# Sheet1.net
KiCad netlist of a schematic drawn in Altium Designer
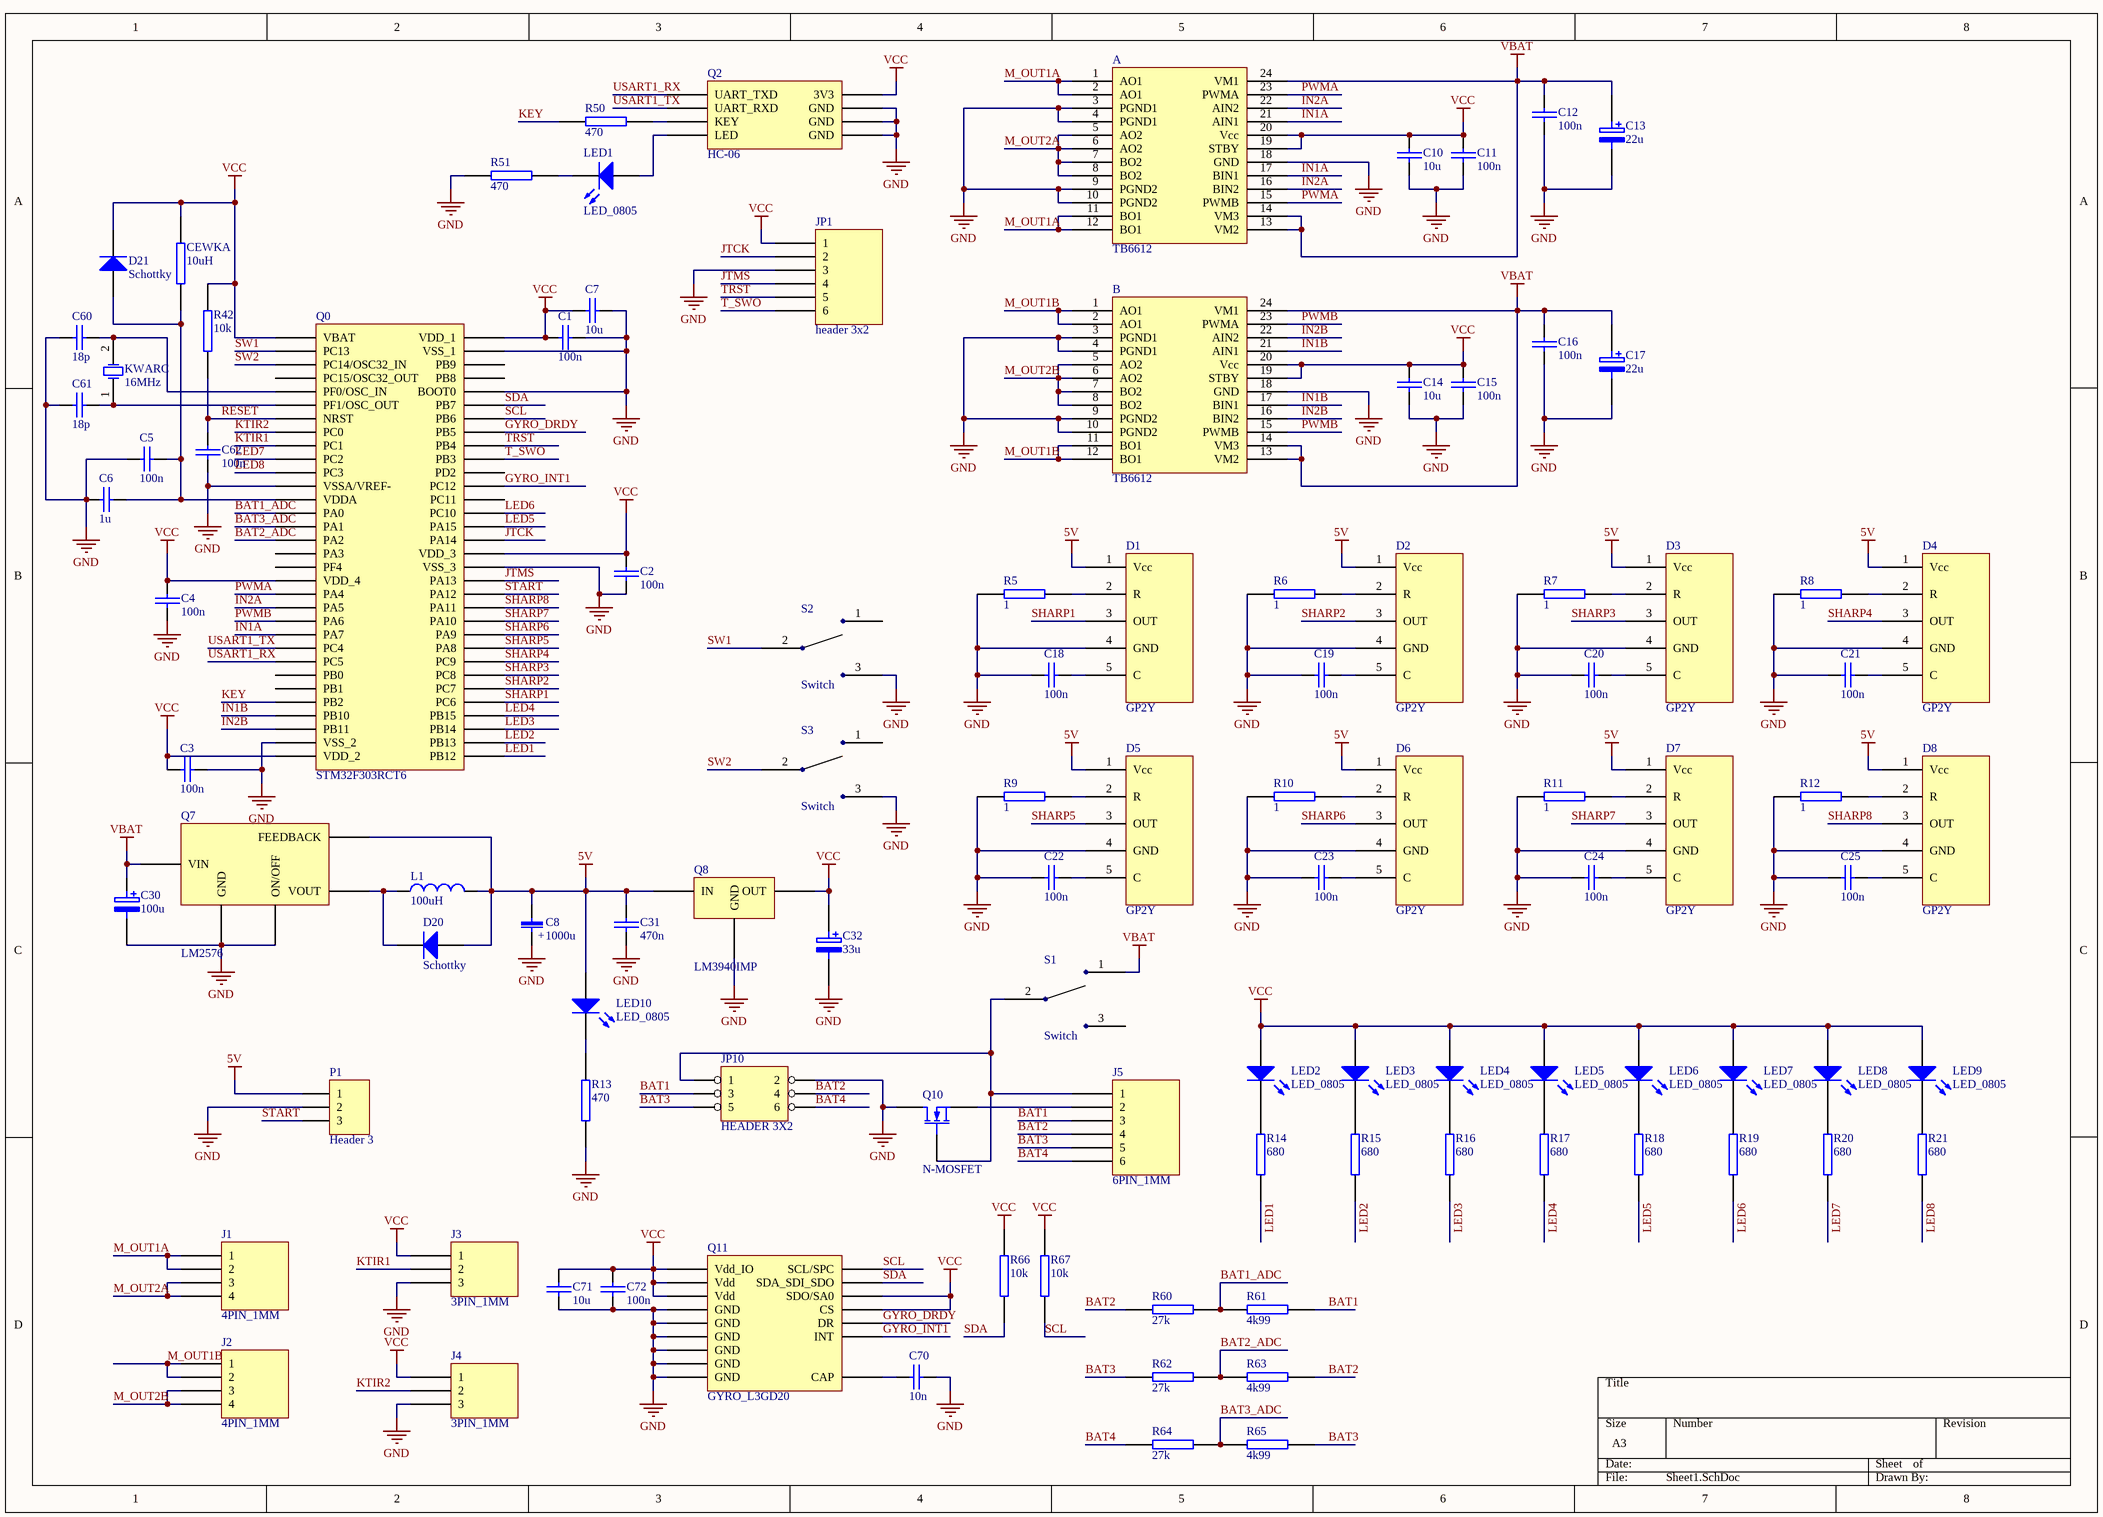
[diagram p0: Sheet1.SchDoc]

(export (version "E")
  (design (tool "Eeschema 10.0.6"))
  (components
    (comp (ref "A")
      (value "TB6612")
      (footprint "SSOP24")
      (libsource (lib "Integrated_Library1") (part "TB6612"))
    )
    (comp (ref "B")
      (value "TB6612")
      (footprint "SSOP24")
      (libsource (lib "Integrated_Library1") (part "TB6612"))
    )
    (comp (ref "C1")
      (value "100n")
      (footprint "0805 CAP")
      (description "Capacitor")
      (libsource (lib "Integrated_Library1") (part "CAP"))
    )
    (comp (ref "C2")
      (value "100n")
      (footprint "0805 CAP")
      (description "Capacitor")
      (libsource (lib "Integrated_Library1") (part "CAP"))
    )
    (comp (ref "C3")
      (value "100n")
      (footprint "0805 CAP")
      (description "Capacitor")
      (libsource (lib "Integrated_Library1") (part "CAP"))
    )
    (comp (ref "C4")
      (value "100n")
      (footprint "0805 CAP")
      (description "Capacitor")
      (libsource (lib "Integrated_Library1") (part "CAP"))
    )
    (comp (ref "C5")
      (value "100n")
      (footprint "0805 CAP")
      (description "Capacitor")
      (libsource (lib "Integrated_Library1") (part "CAP"))
    )
    (comp (ref "C6")
      (value "1u")
      (footprint "0805 CAP")
      (description "Capacitor")
      (libsource (lib "Integrated_Library1") (part "CAP"))
    )
    (comp (ref "C7")
      (value "10u")
      (footprint "0805 CAP")
      (description "Capacitor")
      (libsource (lib "Integrated_Library1") (part "CAP"))
    )
    (comp (ref "C8")
      (value "1000u")
      (footprint "F720J108MMC")
      (description "F720J108MMC")
      (libsource (lib "F720J108MMC") (part "1000u"))
    )
    (comp (ref "C10")
      (value "10u")
      (footprint "0805 CAP")
      (description "Capacitor")
      (libsource (lib "Integrated_Library1") (part "CAP"))
    )
    (comp (ref "C11")
      (value "100n")
      (footprint "0805 CAP")
      (description "Capacitor")
      (libsource (lib "Integrated_Library1") (part "CAP"))
    )
    (comp (ref "C12")
      (value "100n")
      (footprint "0805 CAP")
      (description "Capacitor")
      (libsource (lib "Integrated_Library1") (part "CAP"))
    )
    (comp (ref "C13") (value "22u") (footprint "TANTAL_A") (libsource (lib "Integrated_Library1") (part "E")))
    (comp (ref "C14")
      (value "10u")
      (footprint "0805 CAP")
      (description "Capacitor")
      (libsource (lib "Integrated_Library1") (part "CAP"))
    )
    (comp (ref "C15")
      (value "100n")
      (footprint "0805 CAP")
      (description "Capacitor")
      (libsource (lib "Integrated_Library1") (part "CAP"))
    )
    (comp (ref "C16")
      (value "100n")
      (footprint "0805 CAP")
      (description "Capacitor")
      (libsource (lib "Integrated_Library1") (part "CAP"))
    )
    (comp (ref "C17") (value "22u") (footprint "TANTAL_A") (libsource (lib "Integrated_Library1") (part "E")))
    (comp (ref "C18")
      (value "100n")
      (footprint "0805 CAP")
      (description "Capacitor")
      (libsource (lib "Integrated_Library1") (part "CAP"))
    )
    (comp (ref "C19")
      (value "100n")
      (footprint "0805 CAP")
      (description "Capacitor")
      (libsource (lib "Integrated_Library1") (part "CAP"))
    )
    (comp (ref "C20")
      (value "100n")
      (footprint "0805 CAP")
      (description "Capacitor")
      (libsource (lib "Integrated_Library1") (part "CAP"))
    )
    (comp (ref "C21")
      (value "100n")
      (footprint "0805 CAP")
      (description "Capacitor")
      (libsource (lib "Integrated_Library1") (part "CAP"))
    )
    (comp (ref "C22")
      (value "100n")
      (footprint "0805 CAP")
      (description "Capacitor")
      (libsource (lib "Integrated_Library1") (part "CAP"))
    )
    (comp (ref "C23")
      (value "100n")
      (footprint "0805 CAP")
      (description "Capacitor")
      (libsource (lib "Integrated_Library1") (part "CAP"))
    )
    (comp (ref "C24")
      (value "100n")
      (footprint "0805 CAP")
      (description "Capacitor")
      (libsource (lib "Integrated_Library1") (part "CAP"))
    )
    (comp (ref "C25")
      (value "100n")
      (footprint "0805 CAP")
      (description "Capacitor")
      (libsource (lib "Integrated_Library1") (part "CAP"))
    )
    (comp (ref "C30")
      (value "100u")
      (footprint "TANTAL_C")
      (description "Electrolytic Capacitor")
      (libsource (lib "Integrated_Library1") (part "ELECTRO2"))
    )
    (comp (ref "C31")
      (value "470n")
      (footprint "0805 CAP")
      (description "Capacitor")
      (libsource (lib "Integrated_Library1") (part "CAP"))
    )
    (comp (ref "C32")
      (value "33u")
      (footprint "TANTAL_C")
      (description "Electrolytic Capacitor")
      (libsource (lib "Integrated_Library1") (part "ELECTRO2"))
    )
    (comp (ref "C60")
      (value "18p")
      (footprint "0805 CAP")
      (description "Capacitor")
      (libsource (lib "Integrated_Library1") (part "CAP"))
    )
    (comp (ref "C61")
      (value "18p")
      (footprint "0805 CAP")
      (description "Capacitor")
      (libsource (lib "Integrated_Library1") (part "CAP"))
    )
    (comp (ref "C62")
      (value "100n")
      (footprint "0805 CAP")
      (description "Capacitor")
      (libsource (lib "Integrated_Library1") (part "CAP"))
    )
    (comp (ref "C70")
      (value "10n")
      (footprint "0805")
      (description "Capacitor")
      (libsource (lib "Integrated_Library1") (part "CAP"))
    )
    (comp (ref "C71")
      (value "10u")
      (footprint "0805")
      (description "Capacitor")
      (libsource (lib "Integrated_Library1") (part "CAP"))
    )
    (comp (ref "C72")
      (value "100n")
      (footprint "0805")
      (description "Capacitor")
      (libsource (lib "Integrated_Library1") (part "CAP"))
    )
    (comp (ref "CEWKA") (value "10uH") (footprint "0805") (libsource (lib "Integrated_Library1") (part "R")))
    (comp (ref "D1")
      (value "GP2Y")
      (footprint "gp2y smd")
      (libsource (lib "Integrated_Library1") (part "GP2Y"))
    )
    (comp (ref "D2")
      (value "GP2Y")
      (footprint "gp2y smd")
      (libsource (lib "Integrated_Library1") (part "GP2Y"))
    )
    (comp (ref "D3")
      (value "GP2Y")
      (footprint "gp2y smd")
      (libsource (lib "Integrated_Library1") (part "GP2Y"))
    )
    (comp (ref "D4")
      (value "GP2Y")
      (footprint "gp2y smd")
      (libsource (lib "Integrated_Library1") (part "GP2Y"))
    )
    (comp (ref "D5")
      (value "GP2Y")
      (footprint "gp2y smd")
      (libsource (lib "Integrated_Library1") (part "GP2Y"))
    )
    (comp (ref "D6")
      (value "GP2Y")
      (footprint "gp2y smd")
      (libsource (lib "Integrated_Library1") (part "GP2Y"))
    )
    (comp (ref "D7")
      (value "GP2Y")
      (footprint "gp2y smd")
      (libsource (lib "Integrated_Library1") (part "GP2Y"))
    )
    (comp (ref "D8")
      (value "GP2Y")
      (footprint "gp2y smd")
      (libsource (lib "Integrated_Library1") (part "GP2Y"))
    )
    (comp (ref "D20") (value "Schottky") (footprint "SMB") (libsource (lib "juziuLibrary") (part "Schottky")))
    (comp (ref "D21") (value "Schottky") (footprint "SMB") (libsource (lib "juziuLibrary") (part "Schottky")))
    (comp (ref "J1")
      (value "4PIN_1MM")
      (footprint "CON_1mm_4pin")
      (libsource (lib "juziuLibrary") (part "CON_1MM_4PIN"))
    )
    (comp (ref "J2")
      (value "4PIN_1MM")
      (footprint "CON_1mm_4pin")
      (libsource (lib "juziuLibrary") (part "CON_1MM_4PIN"))
    )
    (comp (ref "J3")
      (value "3PIN_1MM")
      (footprint "CON_1MM_3PIN")
      (libsource (lib "juziuLibrary") (part "CON_1MM_3PIN"))
    )
    (comp (ref "J4")
      (value "3PIN_1MM")
      (footprint "CON_1MM_3PIN")
      (libsource (lib "juziuLibrary") (part "CON_1MM_3PIN"))
    )
    (comp (ref "J5")
      (value "6PIN_1MM")
      (footprint "6pin")
      (libsource (lib "juziuLibrary") (part "CON_1MM_6PIN"))
    )
    (comp (ref "JP1")
      (value "header 3x2")
      (footprint "MM3X2 SMD")
      (libsource (lib "juziuLibrary") (part "CON_1MM_6PIN"))
    )
    (comp (ref "JP10")
      (value "HEADER 3X2")
      (footprint "MM3X2 SMD")
      (libsource (lib "Integrated_Library1") (part "HEADER 3X2"))
    )
    (comp (ref "KWARC")
      (value "16MHz")
      (footprint "KWARC_16M")
      (description "Crystal Oscillator")
      (fields (field (name "PUBLISHER") "Altium Limited"))
      (libsource (lib "juziuLibrary") (part "XTAL"))
    )
    (comp (ref "L1") (value "100uH") (footprint "CEWKA") (libsource (lib "juziuLibrary") (part "CEWKA")))
    (comp (ref "LED1")
      (value "LED_0805")
      (footprint "0805")
      (libsource (lib "juziuLibrary") (part "LED_0805"))
    )
    (comp (ref "LED2")
      (value "LED_0805")
      (footprint "0805")
      (libsource (lib "juziuLibrary") (part "LED_0805"))
    )
    (comp (ref "LED3")
      (value "LED_0805")
      (footprint "0805")
      (libsource (lib "juziuLibrary") (part "LED_0805"))
    )
    (comp (ref "LED4")
      (value "LED_0805")
      (footprint "0805")
      (libsource (lib "juziuLibrary") (part "LED_0805"))
    )
    (comp (ref "LED5")
      (value "LED_0805")
      (footprint "0805")
      (libsource (lib "juziuLibrary") (part "LED_0805"))
    )
    (comp (ref "LED6")
      (value "LED_0805")
      (footprint "0805")
      (libsource (lib "juziuLibrary") (part "LED_0805"))
    )
    (comp (ref "LED7")
      (value "LED_0805")
      (footprint "0805")
      (libsource (lib "juziuLibrary") (part "LED_0805"))
    )
    (comp (ref "LED8")
      (value "LED_0805")
      (footprint "0805")
      (libsource (lib "juziuLibrary") (part "LED_0805"))
    )
    (comp (ref "LED9")
      (value "LED_0805")
      (footprint "0805")
      (libsource (lib "juziuLibrary") (part "LED_0805"))
    )
    (comp (ref "LED10")
      (value "LED_0805")
      (footprint "0805")
      (libsource (lib "juziuLibrary") (part "LED_0805"))
    )
    (comp (ref "P1")
      (value "Header 3")
      (footprint "HDR1X3")
      (description "Header, 3-Pin")
      (fields (field (name "PUBLISHER") "Altium Limited"))
      (libsource (lib "Miscellaneous Connectors") (part "Header 3"))
    )
    (comp (ref "Q0")
      (value "STM32F303RCT6")
      (footprint "STM32F303RCT6")
      (libsource (lib "STM32F303TRCT6") (part "STM32F303RCT6"))
    )
    (comp (ref "Q2")
      (value "HC-06")
      (footprint "PCBComponent_1")
      (description "Bluetooth")
      (libsource (lib "juziuLibrary") (part "Component_1"))
    )
    (comp (ref "Q7") (value "LM2576") (footprint "LM2576") (libsource (lib "juziuLibrary") (part "LM2576")))
    (comp (ref "Q8")
      (value "LM3940IMP")
      (footprint "LM3940IMP")
      (libsource (lib "juziuLibrary") (part "LM3940IMP"))
    )
    (comp (ref "Q10")
      (value "N-MOSFET")
      (footprint "DPAK")
      (libsource (lib "juziuLibrary") (part "n-mosfet"))
    )
    (comp (ref "Q11")
      (value "GYRO_L3GD20")
      (footprint "GYRO_L3GD20")
      (libsource (lib "juziuLibrary") (part "GYRO_L3GD20"))
    )
    (comp (ref "R5") (value "1") (footprint "0805 RES") (libsource (lib "Integrated_Library1") (part "R")))
    (comp (ref "R6") (value "1") (footprint "0805 RES") (libsource (lib "Integrated_Library1") (part "R")))
    (comp (ref "R7") (value "1") (footprint "0805 RES") (libsource (lib "Integrated_Library1") (part "R")))
    (comp (ref "R8") (value "1") (footprint "0805 RES") (libsource (lib "Integrated_Library1") (part "R")))
    (comp (ref "R9") (value "1") (footprint "0805 RES") (libsource (lib "Integrated_Library1") (part "R")))
    (comp (ref "R10") (value "1") (footprint "0805 RES") (libsource (lib "Integrated_Library1") (part "R")))
    (comp (ref "R11") (value "1") (footprint "0805 RES") (libsource (lib "Integrated_Library1") (part "R")))
    (comp (ref "R12") (value "1") (footprint "0805 RES") (libsource (lib "Integrated_Library1") (part "R")))
    (comp (ref "R13") (value "470") (footprint "0805 RES") (libsource (lib "Integrated_Library1") (part "R")))
    (comp (ref "R14") (value "680") (footprint "0805 RES") (libsource (lib "Integrated_Library1") (part "R")))
    (comp (ref "R15") (value "680") (footprint "0805 RES") (libsource (lib "Integrated_Library1") (part "R")))
    (comp (ref "R16") (value "680") (footprint "0805 RES") (libsource (lib "Integrated_Library1") (part "R")))
    (comp (ref "R17") (value "680") (footprint "0805 RES") (libsource (lib "Integrated_Library1") (part "R")))
    (comp (ref "R18") (value "680") (footprint "0805 RES") (libsource (lib "Integrated_Library1") (part "R")))
    (comp (ref "R19") (value "680") (footprint "0805 RES") (libsource (lib "Integrated_Library1") (part "R")))
    (comp (ref "R20") (value "680") (footprint "0805 RES") (libsource (lib "Integrated_Library1") (part "R")))
    (comp (ref "R21") (value "680") (footprint "0805 RES") (libsource (lib "Integrated_Library1") (part "R")))
    (comp (ref "R42") (value "10k") (footprint "0805") (libsource (lib "Integrated_Library1") (part "R")))
    (comp (ref "R50") (value "470") (footprint "0805 RES") (libsource (lib "Integrated_Library1") (part "R")))
    (comp (ref "R51") (value "470") (footprint "0805 RES") (libsource (lib "Integrated_Library1") (part "R")))
    (comp (ref "R60") (value "27k") (footprint "0805") (libsource (lib "Integrated_Library1") (part "R")))
    (comp (ref "R61") (value "4k99") (footprint "0805") (libsource (lib "Integrated_Library1") (part "R")))
    (comp (ref "R62") (value "27k") (footprint "0805") (libsource (lib "Integrated_Library1") (part "R")))
    (comp (ref "R63") (value "4k99") (footprint "0805") (libsource (lib "Integrated_Library1") (part "R")))
    (comp (ref "R64") (value "27k") (footprint "0805") (libsource (lib "Integrated_Library1") (part "R")))
    (comp (ref "R65") (value "4k99") (footprint "0805") (libsource (lib "Integrated_Library1") (part "R")))
    (comp (ref "R66") (value "10k") (footprint "0805") (libsource (lib "Integrated_Library1") (part "R")))
    (comp (ref "R67") (value "10k") (footprint "0805") (libsource (lib "Integrated_Library1") (part "R")))
    (comp (ref "S1") (value "Switch") (footprint "Switch") (libsource (lib "juziuLibrary") (part "Switch")))
    (comp (ref "S2") (value "Switch") (footprint "Switch") (libsource (lib "juziuLibrary") (part "Switch")))
    (comp (ref "S3") (value "Switch") (footprint "Switch") (libsource (lib "juziuLibrary") (part "Switch")))
  )
  (nets
    (net (code "1") (name "/BAT1") (class "Default")
      (node (ref "J5") (pin "3") (pinfunction "3_3") (pintype "passive"))
      (node (ref "JP10") (pin "3") (pinfunction "3_3") (pintype "passive"))
      (node (ref "R61") (pin "1") (pinfunction "1_1") (pintype "passive"))
    )
    (net (code "2") (name "/BAT1_ADC") (class "Default")
      (node (ref "Q0") (pin "14") (pinfunction "PA0_14") (pintype "passive"))
      (node (ref "R60") (pin "1") (pinfunction "1_1") (pintype "passive"))
      (node (ref "R61") (pin "2") (pinfunction "2_2") (pintype "passive"))
    )
    (net (code "3") (name "/BAT2") (class "Default")
      (node (ref "J5") (pin "4") (pinfunction "4_4") (pintype "passive"))
      (node (ref "JP10") (pin "4") (pinfunction "4_4") (pintype "passive"))
      (node (ref "R60") (pin "2") (pinfunction "2_2") (pintype "passive"))
      (node (ref "R63") (pin "1") (pinfunction "1_1") (pintype "passive"))
    )
    (net (code "4") (name "/BAT2_ADC") (class "Default")
      (node (ref "Q0") (pin "16") (pinfunction "PA2_16") (pintype "passive"))
      (node (ref "R62") (pin "1") (pinfunction "1_1") (pintype "passive"))
      (node (ref "R63") (pin "2") (pinfunction "2_2") (pintype "passive"))
    )
    (net (code "5") (name "/BAT3") (class "Default")
      (node (ref "J5") (pin "5") (pinfunction "5_5") (pintype "passive"))
      (node (ref "JP10") (pin "5") (pinfunction "5_5") (pintype "passive"))
      (node (ref "R62") (pin "2") (pinfunction "2_2") (pintype "passive"))
      (node (ref "R65") (pin "1") (pinfunction "1_1") (pintype "passive"))
    )
    (net (code "6") (name "/BAT3_ADC") (class "Default")
      (node (ref "Q0") (pin "15") (pinfunction "PA1_15") (pintype "passive"))
      (node (ref "R64") (pin "1") (pinfunction "1_1") (pintype "passive"))
      (node (ref "R65") (pin "2") (pinfunction "2_2") (pintype "passive"))
    )
    (net (code "7") (name "/BAT4") (class "Default")
      (node (ref "J5") (pin "6") (pinfunction "6_6") (pintype "passive"))
      (node (ref "JP10") (pin "6") (pinfunction "6_6") (pintype "passive"))
      (node (ref "R64") (pin "2") (pinfunction "2_2") (pintype "passive"))
    )
    (net (code "8") (name "/GYRO_DRDY") (class "Default")
      (node (ref "Q0") (pin "57") (pinfunction "PB5_57") (pintype "passive"))
      (node (ref "Q11") (pin "6") (pinfunction "DR_6") (pintype "passive"))
    )
    (net (code "9") (name "/GYRO_INT1") (class "Default")
      (node (ref "Q0") (pin "53") (pinfunction "PC12_53") (pintype "passive"))
      (node (ref "Q11") (pin "7") (pinfunction "INT_7") (pintype "passive"))
    )
    (net (code "10") (name "/IN1A") (class "Default")
      (node (ref "A") (pin "17") (pinfunction "BIN1_17") (pintype "passive"))
      (node (ref "A") (pin "21") (pinfunction "AIN1_21") (pintype "passive"))
      (node (ref "Q0") (pin "23") (pinfunction "PA7_23") (pintype "passive"))
    )
    (net (code "11") (name "/IN1B") (class "Default")
      (node (ref "B") (pin "17") (pinfunction "BIN1_17") (pintype "passive"))
      (node (ref "B") (pin "21") (pinfunction "AIN1_21") (pintype "passive"))
      (node (ref "Q0") (pin "29") (pinfunction "PB10_29") (pintype "passive"))
    )
    (net (code "12") (name "/IN2A") (class "Default")
      (node (ref "A") (pin "16") (pinfunction "BIN2_16") (pintype "passive"))
      (node (ref "A") (pin "22") (pinfunction "AIN2_22") (pintype "passive"))
      (node (ref "Q0") (pin "21") (pinfunction "PA5_21") (pintype "passive"))
    )
    (net (code "13") (name "/IN2B") (class "Default")
      (node (ref "B") (pin "16") (pinfunction "BIN2_16") (pintype "passive"))
      (node (ref "B") (pin "22") (pinfunction "AIN2_22") (pintype "passive"))
      (node (ref "Q0") (pin "30") (pinfunction "PB11_30") (pintype "passive"))
    )
    (net (code "14") (name "/JTCK") (class "Default")
      (node (ref "JP1") (pin "2") (pinfunction "2_2") (pintype "passive"))
      (node (ref "Q0") (pin "49") (pinfunction "PA14_49") (pintype "passive"))
    )
    (net (code "15") (name "/JTMS") (class "Default")
      (node (ref "JP1") (pin "4") (pinfunction "4_4") (pintype "passive"))
      (node (ref "Q0") (pin "46") (pinfunction "PA13_46") (pintype "passive"))
    )
    (net (code "16") (name "/KEY") (class "Default")
      (node (ref "Q0") (pin "28") (pinfunction "PB2_28") (pintype "passive"))
      (node (ref "R50") (pin "1") (pinfunction "1_1") (pintype "passive"))
    )
    (net (code "17") (name "/KTIR1") (class "Default")
      (node (ref "J3") (pin "2") (pinfunction "2_2") (pintype "passive"))
      (node (ref "Q0") (pin "9") (pinfunction "PC1_9") (pintype "passive"))
    )
    (net (code "18") (name "/KTIR2") (class "Default")
      (node (ref "J4") (pin "2") (pinfunction "2_2") (pintype "passive"))
      (node (ref "Q0") (pin "8") (pinfunction "PC0_8") (pintype "passive"))
    )
    (net (code "19") (name "/LED1") (class "Default")
      (node (ref "Q0") (pin "33") (pinfunction "PB12_33") (pintype "passive"))
      (node (ref "R14") (pin "1") (pinfunction "1_1") (pintype "passive"))
    )
    (net (code "20") (name "/LED2") (class "Default")
      (node (ref "Q0") (pin "34") (pinfunction "PB13_34") (pintype "passive"))
      (node (ref "R15") (pin "1") (pinfunction "1_1") (pintype "passive"))
    )
    (net (code "21") (name "/LED3") (class "Default")
      (node (ref "Q0") (pin "35") (pinfunction "PB14_35") (pintype "passive"))
      (node (ref "R16") (pin "1") (pinfunction "1_1") (pintype "passive"))
    )
    (net (code "22") (name "/LED4") (class "Default")
      (node (ref "Q0") (pin "36") (pinfunction "PB15_36") (pintype "passive"))
      (node (ref "R17") (pin "1") (pinfunction "1_1") (pintype "passive"))
    )
    (net (code "23") (name "/LED5") (class "Default")
      (node (ref "Q0") (pin "50") (pinfunction "PA15_50") (pintype "passive"))
      (node (ref "R18") (pin "1") (pinfunction "1_1") (pintype "passive"))
    )
    (net (code "24") (name "/LED6") (class "Default")
      (node (ref "Q0") (pin "51") (pinfunction "PC10_51") (pintype "passive"))
      (node (ref "R19") (pin "1") (pinfunction "1_1") (pintype "passive"))
    )
    (net (code "25") (name "/LED7") (class "Default")
      (node (ref "Q0") (pin "10") (pinfunction "PC2_10") (pintype "passive"))
      (node (ref "R20") (pin "1") (pinfunction "1_1") (pintype "passive"))
    )
    (net (code "26") (name "/LED8") (class "Default")
      (node (ref "Q0") (pin "11") (pinfunction "PC3_11") (pintype "passive"))
      (node (ref "R21") (pin "1") (pinfunction "1_1") (pintype "passive"))
    )
    (net (code "27") (name "/M_OUT1A") (class "Default")
      (node (ref "A") (pin "1") (pinfunction "AO1_1") (pintype "passive"))
      (node (ref "A") (pin "11") (pinfunction "BO1_11") (pintype "passive"))
      (node (ref "A") (pin "12") (pinfunction "BO1_12") (pintype "passive"))
      (node (ref "A") (pin "2") (pinfunction "AO1_2") (pintype "passive"))
      (node (ref "J1") (pin "1") (pinfunction "1_1") (pintype "passive"))
      (node (ref "J1") (pin "2") (pinfunction "2_2") (pintype "passive"))
    )
    (net (code "28") (name "/M_OUT1B") (class "Default")
      (node (ref "B") (pin "1") (pinfunction "AO1_1") (pintype "passive"))
      (node (ref "B") (pin "11") (pinfunction "BO1_11") (pintype "passive"))
      (node (ref "B") (pin "12") (pinfunction "BO1_12") (pintype "passive"))
      (node (ref "B") (pin "2") (pinfunction "AO1_2") (pintype "passive"))
      (node (ref "J2") (pin "1") (pinfunction "1_1") (pintype "passive"))
      (node (ref "J2") (pin "2") (pinfunction "2_2") (pintype "passive"))
    )
    (net (code "29") (name "/M_OUT2A") (class "Default")
      (node (ref "A") (pin "5") (pinfunction "AO2_5") (pintype "passive"))
      (node (ref "A") (pin "6") (pinfunction "AO2_6") (pintype "passive"))
      (node (ref "A") (pin "7") (pinfunction "BO2_7") (pintype "passive"))
      (node (ref "A") (pin "8") (pinfunction "BO2_8") (pintype "passive"))
      (node (ref "J1") (pin "3") (pinfunction "3_3") (pintype "passive"))
      (node (ref "J1") (pin "4") (pinfunction "4_4") (pintype "passive"))
    )
    (net (code "30") (name "/M_OUT2B") (class "Default")
      (node (ref "B") (pin "5") (pinfunction "AO2_5") (pintype "passive"))
      (node (ref "B") (pin "6") (pinfunction "AO2_6") (pintype "passive"))
      (node (ref "B") (pin "7") (pinfunction "BO2_7") (pintype "passive"))
      (node (ref "B") (pin "8") (pinfunction "BO2_8") (pintype "passive"))
      (node (ref "J2") (pin "3") (pinfunction "3_3") (pintype "passive"))
      (node (ref "J2") (pin "4") (pinfunction "4_4") (pintype "passive"))
    )
    (net (code "31") (name "/PWMA") (class "Default")
      (node (ref "A") (pin "15") (pinfunction "PWMB_15") (pintype "passive"))
      (node (ref "A") (pin "23") (pinfunction "PWMA_23") (pintype "passive"))
      (node (ref "Q0") (pin "20") (pinfunction "PA4_20") (pintype "passive"))
    )
    (net (code "32") (name "/PWMB") (class "Default")
      (node (ref "B") (pin "15") (pinfunction "PWMB_15") (pintype "passive"))
      (node (ref "B") (pin "23") (pinfunction "PWMA_23") (pintype "passive"))
      (node (ref "Q0") (pin "22") (pinfunction "PA6_22") (pintype "passive"))
    )
    (net (code "33") (name "/RESET") (class "Default")
      (node (ref "C62") (pin "1") (pinfunction "1_1") (pintype "passive"))
      (node (ref "Q0") (pin "7") (pinfunction "NRST_7") (pintype "passive"))
      (node (ref "R42") (pin "1") (pinfunction "1_1") (pintype "passive"))
    )
    (net (code "34") (name "/SCL") (class "Default")
      (node (ref "Q0") (pin "58") (pinfunction "PB6_58") (pintype "passive"))
      (node (ref "Q11") (pin "2") (pinfunction "SCL/SPC_2") (pintype "passive"))
      (node (ref "R67") (pin "2") (pinfunction "2_2") (pintype "passive"))
    )
    (net (code "35") (name "/SDA") (class "Default")
      (node (ref "Q0") (pin "59") (pinfunction "PB7_59") (pintype "passive"))
      (node (ref "Q11") (pin "3") (pinfunction "SDA_SDI_SDO_3") (pintype "passive"))
      (node (ref "R66") (pin "2") (pinfunction "2_2") (pintype "passive"))
    )
    (net (code "36") (name "/SHARP1") (class "Default")
      (node (ref "D1") (pin "3") (pinfunction "OUT_3") (pintype "passive"))
      (node (ref "Q0") (pin "37") (pinfunction "PC6_37") (pintype "passive"))
    )
    (net (code "37") (name "/SHARP2") (class "Default")
      (node (ref "D2") (pin "3") (pinfunction "OUT_3") (pintype "passive"))
      (node (ref "Q0") (pin "38") (pinfunction "PC7_38") (pintype "passive"))
    )
    (net (code "38") (name "/SHARP3") (class "Default")
      (node (ref "D3") (pin "3") (pinfunction "OUT_3") (pintype "passive"))
      (node (ref "Q0") (pin "39") (pinfunction "PC8_39") (pintype "passive"))
    )
    (net (code "39") (name "/SHARP4") (class "Default")
      (node (ref "D4") (pin "3") (pinfunction "OUT_3") (pintype "passive"))
      (node (ref "Q0") (pin "40") (pinfunction "PC9_40") (pintype "passive"))
    )
    (net (code "40") (name "/SHARP5") (class "Default")
      (node (ref "D5") (pin "3") (pinfunction "OUT_3") (pintype "passive"))
      (node (ref "Q0") (pin "41") (pinfunction "PA8_41") (pintype "passive"))
    )
    (net (code "41") (name "/SHARP6") (class "Default")
      (node (ref "D6") (pin "3") (pinfunction "OUT_3") (pintype "passive"))
      (node (ref "Q0") (pin "42") (pinfunction "PA9_42") (pintype "passive"))
    )
    (net (code "42") (name "/SHARP7") (class "Default")
      (node (ref "D7") (pin "3") (pinfunction "OUT_3") (pintype "passive"))
      (node (ref "Q0") (pin "43") (pinfunction "PA10_43") (pintype "passive"))
    )
    (net (code "43") (name "/SHARP8") (class "Default")
      (node (ref "D8") (pin "3") (pinfunction "OUT_3") (pintype "passive"))
      (node (ref "Q0") (pin "44") (pinfunction "PA11_44") (pintype "passive"))
    )
    (net (code "44") (name "/START") (class "Default")
      (node (ref "P1") (pin "3") (pinfunction "3_3") (pintype "passive"))
      (node (ref "Q0") (pin "45") (pinfunction "PA12_45") (pintype "passive"))
    )
    (net (code "45") (name "/SW1") (class "Default")
      (node (ref "Q0") (pin "2") (pinfunction "PC13_2") (pintype "passive"))
      (node (ref "S2") (pin "2") (pintype "passive"))
    )
    (net (code "46") (name "/SW2") (class "Default")
      (node (ref "Q0") (pin "3") (pinfunction "PC14/OSC32_IN_3") (pintype "passive"))
      (node (ref "S3") (pin "2") (pintype "passive"))
    )
    (net (code "47") (name "/TRST") (class "Default")
      (node (ref "JP1") (pin "5") (pinfunction "5_5") (pintype "passive"))
      (node (ref "Q0") (pin "56") (pinfunction "PB4_56") (pintype "passive"))
    )
    (net (code "48") (name "/T_SWO") (class "Default")
      (node (ref "JP1") (pin "6") (pinfunction "6_6") (pintype "passive"))
      (node (ref "Q0") (pin "55") (pinfunction "PB3_55") (pintype "passive"))
    )
    (net (code "49") (name "/USART1_RX") (class "Default")
      (node (ref "Q0") (pin "25") (pinfunction "PC5_25") (pintype "passive"))
      (node (ref "Q2") (pin "1") (pinfunction "UART_TXD_1") (pintype "passive"))
    )
    (net (code "50") (name "/USART1_TX") (class "Default")
      (node (ref "Q0") (pin "24") (pinfunction "PC4_24") (pintype "passive"))
      (node (ref "Q2") (pin "2") (pinfunction "UART_RXD_2") (pintype "passive"))
    )
    (net (code "51") (name "5V") (class "Default")
      (node (ref "C31") (pin "2") (pinfunction "2_2") (pintype "passive"))
      (node (ref "C8") (pin "1") (pinfunction "1_1") (pintype "passive"))
      (node (ref "D1") (pin "1") (pinfunction "Vcc_1") (pintype "passive"))
      (node (ref "D2") (pin "1") (pinfunction "Vcc_1") (pintype "passive"))
      (node (ref "D20") (pin "1") (pinfunction "A_1") (pintype "passive"))
      (node (ref "D3") (pin "1") (pinfunction "Vcc_1") (pintype "passive"))
      (node (ref "D4") (pin "1") (pinfunction "Vcc_1") (pintype "passive"))
      (node (ref "D5") (pin "1") (pinfunction "Vcc_1") (pintype "passive"))
      (node (ref "D6") (pin "1") (pinfunction "Vcc_1") (pintype "passive"))
      (node (ref "D7") (pin "1") (pinfunction "Vcc_1") (pintype "passive"))
      (node (ref "D8") (pin "1") (pinfunction "Vcc_1") (pintype "passive"))
      (node (ref "L1") (pin "2") (pinfunction "2_2") (pintype "passive"))
      (node (ref "LED10") (pin "2") (pinfunction "A_2") (pintype "passive"))
      (node (ref "P1") (pin "1") (pinfunction "1_1") (pintype "passive"))
      (node (ref "Q7") (pin "4") (pinfunction "FEEDBACK_4") (pintype "passive"))
      (node (ref "Q8") (pin "IN") (pinfunction "IN_IN") (pintype "passive"))
    )
    (net (code "52") (name "GND") (class "Default")
      (node (ref "A") (pin "10") (pinfunction "PGND2_10") (pintype "passive"))
      (node (ref "A") (pin "18") (pinfunction "GND_18") (pintype "passive"))
      (node (ref "A") (pin "3") (pinfunction "PGND1_3") (pintype "passive"))
      (node (ref "A") (pin "4") (pinfunction "PGND1_4") (pintype "passive"))
      (node (ref "A") (pin "9") (pinfunction "PGND2_9") (pintype "passive"))
      (node (ref "B") (pin "10") (pinfunction "PGND2_10") (pintype "passive"))
      (node (ref "B") (pin "18") (pinfunction "GND_18") (pintype "passive"))
      (node (ref "B") (pin "3") (pinfunction "PGND1_3") (pintype "passive"))
      (node (ref "B") (pin "4") (pinfunction "PGND1_4") (pintype "passive"))
      (node (ref "B") (pin "9") (pinfunction "PGND2_9") (pintype "passive"))
      (node (ref "C1") (pin "2") (pinfunction "2_2") (pintype "passive"))
      (node (ref "C10") (pin "2") (pinfunction "2_2") (pintype "passive"))
      (node (ref "C11") (pin "2") (pinfunction "2_2") (pintype "passive"))
      (node (ref "C12") (pin "2") (pinfunction "2_2") (pintype "passive"))
      (node (ref "C13") (pin "2") (pinfunction "2_2") (pintype "passive"))
      (node (ref "C14") (pin "2") (pinfunction "2_2") (pintype "passive"))
      (node (ref "C15") (pin "2") (pinfunction "2_2") (pintype "passive"))
      (node (ref "C16") (pin "2") (pinfunction "2_2") (pintype "passive"))
      (node (ref "C17") (pin "2") (pinfunction "2_2") (pintype "passive"))
      (node (ref "C18") (pin "1") (pinfunction "1_1") (pintype "passive"))
      (node (ref "C19") (pin "1") (pinfunction "1_1") (pintype "passive"))
      (node (ref "C2") (pin "2") (pinfunction "2_2") (pintype "passive"))
      (node (ref "C20") (pin "1") (pinfunction "1_1") (pintype "passive"))
      (node (ref "C21") (pin "1") (pinfunction "1_1") (pintype "passive"))
      (node (ref "C22") (pin "1") (pinfunction "1_1") (pintype "passive"))
      (node (ref "C23") (pin "1") (pinfunction "1_1") (pintype "passive"))
      (node (ref "C24") (pin "1") (pinfunction "1_1") (pintype "passive"))
      (node (ref "C25") (pin "1") (pinfunction "1_1") (pintype "passive"))
      (node (ref "C3") (pin "2") (pinfunction "2_2") (pintype "passive"))
      (node (ref "C30") (pin "2") (pinfunction "2_2") (pintype "passive"))
      (node (ref "C31") (pin "1") (pinfunction "1_1") (pintype "passive"))
      (node (ref "C32") (pin "2") (pinfunction "2_2") (pintype "passive"))
      (node (ref "C4") (pin "2") (pinfunction "2_2") (pintype "passive"))
      (node (ref "C5") (pin "2") (pinfunction "2_2") (pintype "passive"))
      (node (ref "C6") (pin "1") (pinfunction "1_1") (pintype "passive"))
      (node (ref "C60") (pin "1") (pinfunction "1_1") (pintype "passive"))
      (node (ref "C61") (pin "2") (pinfunction "2_2") (pintype "passive"))
      (node (ref "C62") (pin "2") (pinfunction "2_2") (pintype "passive"))
      (node (ref "C7") (pin "2") (pinfunction "2_2") (pintype "passive"))
      (node (ref "C70") (pin "1") (pinfunction "1_1") (pintype "passive"))
      (node (ref "C71") (pin "2") (pinfunction "2_2") (pintype "passive"))
      (node (ref "C72") (pin "2") (pinfunction "2_2") (pintype "passive"))
      (node (ref "C8") (pin "2") (pinfunction "2_2") (pintype "passive"))
      (node (ref "D1") (pin "4") (pinfunction "GND_4") (pintype "passive"))
      (node (ref "D2") (pin "4") (pinfunction "GND_4") (pintype "passive"))
      (node (ref "D3") (pin "4") (pinfunction "GND_4") (pintype "passive"))
      (node (ref "D4") (pin "4") (pinfunction "GND_4") (pintype "passive"))
      (node (ref "D5") (pin "4") (pinfunction "GND_4") (pintype "passive"))
      (node (ref "D6") (pin "4") (pinfunction "GND_4") (pintype "passive"))
      (node (ref "D7") (pin "4") (pinfunction "GND_4") (pintype "passive"))
      (node (ref "D8") (pin "4") (pinfunction "GND_4") (pintype "passive"))
      (node (ref "J3") (pin "3") (pinfunction "3_3") (pintype "passive"))
      (node (ref "J4") (pin "3") (pinfunction "3_3") (pintype "passive"))
      (node (ref "JP1") (pin "3") (pinfunction "3_3") (pintype "passive"))
      (node (ref "JP10") (pin "2") (pinfunction "2_2") (pintype "passive"))
      (node (ref "P1") (pin "2") (pinfunction "2_2") (pintype "passive"))
      (node (ref "Q0") (pin "12") (pinfunction "VSSA/VREF-_12") (pintype "passive"))
      (node (ref "Q0") (pin "31") (pinfunction "VSS_2_31") (pintype "passive"))
      (node (ref "Q0") (pin "47") (pinfunction "VSS_3_47") (pintype "passive"))
      (node (ref "Q0") (pin "60") (pinfunction "BOOT0_60") (pintype "passive"))
      (node (ref "Q0") (pin "63") (pinfunction "VSS_1_63") (pintype "passive"))
      (node (ref "Q10") (pin "2") (pinfunction "D_2") (pintype "passive"))
      (node (ref "Q11") (pin "10") (pinfunction "GND_10") (pintype "passive"))
      (node (ref "Q11") (pin "11") (pinfunction "GND_11") (pintype "passive"))
      (node (ref "Q11") (pin "12") (pinfunction "GND_12") (pintype "passive"))
      (node (ref "Q11") (pin "13") (pinfunction "GND_13") (pintype "passive"))
      (node (ref "Q11") (pin "8") (pinfunction "GND_8") (pintype "passive"))
      (node (ref "Q11") (pin "9") (pinfunction "GND_9") (pintype "passive"))
      (node (ref "Q2") (pin "4") (pinfunction "GND_4") (pintype "passive"))
      (node (ref "Q2") (pin "5") (pinfunction "GND_5") (pintype "passive"))
      (node (ref "Q2") (pin "6") (pinfunction "GND_6") (pintype "passive"))
      (node (ref "Q7") (pin "3") (pinfunction "GND_3") (pintype "passive"))
      (node (ref "Q7") (pin "5") (pinfunction "ON/OFF_5") (pintype "passive"))
      (node (ref "Q8") (pin "GND") (pinfunction "GND_GND") (pintype "passive"))
      (node (ref "R10") (pin "1") (pinfunction "1_1") (pintype "passive"))
      (node (ref "R11") (pin "1") (pinfunction "1_1") (pintype "passive"))
      (node (ref "R12") (pin "1") (pinfunction "1_1") (pintype "passive"))
      (node (ref "R13") (pin "1") (pinfunction "1_1") (pintype "passive"))
      (node (ref "R5") (pin "1") (pinfunction "1_1") (pintype "passive"))
      (node (ref "R51") (pin "1") (pinfunction "1_1") (pintype "passive"))
      (node (ref "R6") (pin "1") (pinfunction "1_1") (pintype "passive"))
      (node (ref "R7") (pin "1") (pinfunction "1_1") (pintype "passive"))
      (node (ref "R8") (pin "1") (pinfunction "1_1") (pintype "passive"))
      (node (ref "R9") (pin "1") (pinfunction "1_1") (pintype "passive"))
      (node (ref "S2") (pin "3") (pintype "passive"))
      (node (ref "S3") (pin "3") (pintype "passive"))
    )
    (net (code "53") (name "Net-(D1-C)") (class "Default")
      (node (ref "C18") (pin "2") (pinfunction "2_2") (pintype "passive"))
      (node (ref "D1") (pin "5") (pinfunction "C_5") (pintype "passive"))
    )
    (net (code "54") (name "Net-(D1-R)") (class "Default")
      (node (ref "D1") (pin "2") (pinfunction "R_2") (pintype "passive"))
      (node (ref "R5") (pin "2") (pinfunction "2_2") (pintype "passive"))
    )
    (net (code "55") (name "Net-(D2-C)") (class "Default")
      (node (ref "C19") (pin "2") (pinfunction "2_2") (pintype "passive"))
      (node (ref "D2") (pin "5") (pinfunction "C_5") (pintype "passive"))
    )
    (net (code "56") (name "Net-(D2-R)") (class "Default")
      (node (ref "D2") (pin "2") (pinfunction "R_2") (pintype "passive"))
      (node (ref "R6") (pin "2") (pinfunction "2_2") (pintype "passive"))
    )
    (net (code "57") (name "Net-(D3-C)") (class "Default")
      (node (ref "C20") (pin "2") (pinfunction "2_2") (pintype "passive"))
      (node (ref "D3") (pin "5") (pinfunction "C_5") (pintype "passive"))
    )
    (net (code "58") (name "Net-(D3-R)") (class "Default")
      (node (ref "D3") (pin "2") (pinfunction "R_2") (pintype "passive"))
      (node (ref "R7") (pin "2") (pinfunction "2_2") (pintype "passive"))
    )
    (net (code "59") (name "Net-(D4-C)") (class "Default")
      (node (ref "C21") (pin "2") (pinfunction "2_2") (pintype "passive"))
      (node (ref "D4") (pin "5") (pinfunction "C_5") (pintype "passive"))
    )
    (net (code "60") (name "Net-(D4-R)") (class "Default")
      (node (ref "D4") (pin "2") (pinfunction "R_2") (pintype "passive"))
      (node (ref "R8") (pin "2") (pinfunction "2_2") (pintype "passive"))
    )
    (net (code "61") (name "Net-(D5-C)") (class "Default")
      (node (ref "C22") (pin "2") (pinfunction "2_2") (pintype "passive"))
      (node (ref "D5") (pin "5") (pinfunction "C_5") (pintype "passive"))
    )
    (net (code "62") (name "Net-(D5-R)") (class "Default")
      (node (ref "D5") (pin "2") (pinfunction "R_2") (pintype "passive"))
      (node (ref "R9") (pin "2") (pinfunction "2_2") (pintype "passive"))
    )
    (net (code "63") (name "Net-(D6-C)") (class "Default")
      (node (ref "C23") (pin "2") (pinfunction "2_2") (pintype "passive"))
      (node (ref "D6") (pin "5") (pinfunction "C_5") (pintype "passive"))
    )
    (net (code "64") (name "Net-(D6-R)") (class "Default")
      (node (ref "D6") (pin "2") (pinfunction "R_2") (pintype "passive"))
      (node (ref "R10") (pin "2") (pinfunction "2_2") (pintype "passive"))
    )
    (net (code "65") (name "Net-(D7-C)") (class "Default")
      (node (ref "C24") (pin "2") (pinfunction "2_2") (pintype "passive"))
      (node (ref "D7") (pin "5") (pinfunction "C_5") (pintype "passive"))
    )
    (net (code "66") (name "Net-(D7-R)") (class "Default")
      (node (ref "D7") (pin "2") (pinfunction "R_2") (pintype "passive"))
      (node (ref "R11") (pin "2") (pinfunction "2_2") (pintype "passive"))
    )
    (net (code "67") (name "Net-(D8-C)") (class "Default")
      (node (ref "C25") (pin "2") (pinfunction "2_2") (pintype "passive"))
      (node (ref "D8") (pin "5") (pinfunction "C_5") (pintype "passive"))
    )
    (net (code "68") (name "Net-(D8-R)") (class "Default")
      (node (ref "D8") (pin "2") (pinfunction "R_2") (pintype "passive"))
      (node (ref "R12") (pin "2") (pinfunction "2_2") (pintype "passive"))
    )
    (net (code "69") (name "Net-(D20-K)") (class "Default")
      (node (ref "D20") (pin "2") (pinfunction "K_2") (pintype "passive"))
      (node (ref "L1") (pin "1") (pinfunction "1_1") (pintype "passive"))
      (node (ref "Q7") (pin "2") (pinfunction "VOUT_2") (pintype "passive"))
    )
    (net (code "70") (name "Net-(D21-A)") (class "Default")
      (node (ref "C5") (pin "1") (pinfunction "1_1") (pintype "passive"))
      (node (ref "C6") (pin "2") (pinfunction "2_2") (pintype "passive"))
      (node (ref "CEWKA") (pin "1") (pinfunction "1_1") (pintype "passive"))
      (node (ref "D21") (pin "1") (pinfunction "A_1") (pintype "passive"))
      (node (ref "Q0") (pin "13") (pinfunction "VDDA_13") (pintype "passive"))
    )
    (net (code "71") (name "Net-(KWARC-OSC1)") (class "Default")
      (node (ref "C61") (pin "1") (pinfunction "1_1") (pintype "passive"))
      (node (ref "KWARC") (pin "1") (pinfunction "OSC1_1") (pintype "passive"))
      (node (ref "Q0") (pin "6") (pinfunction "PF1/OSC_OUT_6") (pintype "passive"))
    )
    (net (code "72") (name "Net-(KWARC-OSC2)") (class "Default")
      (node (ref "C60") (pin "2") (pinfunction "2_2") (pintype "passive"))
      (node (ref "KWARC") (pin "2") (pinfunction "OSC2_2") (pintype "passive"))
      (node (ref "Q0") (pin "5") (pinfunction "PF0/OSC_IN_5") (pintype "passive"))
    )
    (net (code "73") (name "Net-(LED1-A)") (class "Default")
      (node (ref "LED1") (pin "2") (pinfunction "A_2") (pintype "passive"))
      (node (ref "Q2") (pin "7") (pinfunction "LED_7") (pintype "passive"))
    )
    (net (code "74") (name "Net-(LED1-K)") (class "Default")
      (node (ref "LED1") (pin "1") (pinfunction "K_1") (pintype "passive"))
      (node (ref "R51") (pin "2") (pinfunction "2_2") (pintype "passive"))
    )
    (net (code "75") (name "Net-(LED2-K)") (class "Default")
      (node (ref "LED2") (pin "1") (pinfunction "K_1") (pintype "passive"))
      (node (ref "R14") (pin "2") (pinfunction "2_2") (pintype "passive"))
    )
    (net (code "76") (name "Net-(LED3-K)") (class "Default")
      (node (ref "LED3") (pin "1") (pinfunction "K_1") (pintype "passive"))
      (node (ref "R15") (pin "2") (pinfunction "2_2") (pintype "passive"))
    )
    (net (code "77") (name "Net-(LED4-K)") (class "Default")
      (node (ref "LED4") (pin "1") (pinfunction "K_1") (pintype "passive"))
      (node (ref "R16") (pin "2") (pinfunction "2_2") (pintype "passive"))
    )
    (net (code "78") (name "Net-(LED5-K)") (class "Default")
      (node (ref "LED5") (pin "1") (pinfunction "K_1") (pintype "passive"))
      (node (ref "R17") (pin "2") (pinfunction "2_2") (pintype "passive"))
    )
    (net (code "79") (name "Net-(LED6-K)") (class "Default")
      (node (ref "LED6") (pin "1") (pinfunction "K_1") (pintype "passive"))
      (node (ref "R18") (pin "2") (pinfunction "2_2") (pintype "passive"))
    )
    (net (code "80") (name "Net-(LED7-K)") (class "Default")
      (node (ref "LED7") (pin "1") (pinfunction "K_1") (pintype "passive"))
      (node (ref "R19") (pin "2") (pinfunction "2_2") (pintype "passive"))
    )
    (net (code "81") (name "Net-(LED8-K)") (class "Default")
      (node (ref "LED8") (pin "1") (pinfunction "K_1") (pintype "passive"))
      (node (ref "R20") (pin "2") (pinfunction "2_2") (pintype "passive"))
    )
    (net (code "82") (name "Net-(LED9-K)") (class "Default")
      (node (ref "LED9") (pin "1") (pinfunction "K_1") (pintype "passive"))
      (node (ref "R21") (pin "2") (pinfunction "2_2") (pintype "passive"))
    )
    (net (code "83") (name "Net-(LED10-K)") (class "Default")
      (node (ref "LED10") (pin "1") (pinfunction "K_1") (pintype "passive"))
      (node (ref "R13") (pin "2") (pinfunction "2_2") (pintype "passive"))
    )
    (net (code "84") (name "Net-(Q2-KEY)") (class "Default")
      (node (ref "Q2") (pin "8") (pinfunction "KEY_8") (pintype "passive"))
      (node (ref "R50") (pin "2") (pinfunction "2_2") (pintype "passive"))
    )
    (net (code "85") (name "Net-(Q10-G)") (class "Default")
      (node (ref "J5") (pin "1") (pinfunction "1_1") (pintype "passive"))
      (node (ref "JP10") (pin "1") (pinfunction "1_1") (pintype "passive"))
      (node (ref "Q10") (pin "1") (pinfunction "G_1") (pintype "passive"))
      (node (ref "S1") (pin "2") (pintype "passive"))
    )
    (net (code "86") (name "Net-(Q10-S)") (class "Default")
      (node (ref "J5") (pin "2") (pinfunction "2_2") (pintype "passive"))
      (node (ref "Q10") (pin "3") (pinfunction "S_3") (pintype "passive"))
    )
    (net (code "87") (name "Net-(Q11-CAP)") (class "Default")
      (node (ref "C70") (pin "2") (pinfunction "2_2") (pintype "passive"))
      (node (ref "Q11") (pin "14") (pinfunction "CAP_14") (pintype "passive"))
    )
    (net (code "88") (name "VBAT") (class "Default")
      (node (ref "A") (pin "13") (pinfunction "VM2_13") (pintype "passive"))
      (node (ref "A") (pin "14") (pinfunction "VM3_14") (pintype "passive"))
      (node (ref "A") (pin "24") (pinfunction "VM1_24") (pintype "passive"))
      (node (ref "B") (pin "13") (pinfunction "VM2_13") (pintype "passive"))
      (node (ref "B") (pin "14") (pinfunction "VM3_14") (pintype "passive"))
      (node (ref "B") (pin "24") (pinfunction "VM1_24") (pintype "passive"))
      (node (ref "C12") (pin "1") (pinfunction "1_1") (pintype "passive"))
      (node (ref "C13") (pin "1") (pinfunction "1_1") (pintype "passive"))
      (node (ref "C16") (pin "1") (pinfunction "1_1") (pintype "passive"))
      (node (ref "C17") (pin "1") (pinfunction "1_1") (pintype "passive"))
      (node (ref "C30") (pin "1") (pinfunction "1_1") (pintype "passive"))
      (node (ref "Q7") (pin "1") (pinfunction "VIN_1") (pintype "passive"))
      (node (ref "S1") (pin "1") (pintype "passive"))
    )
    (net (code "89") (name "VCC") (class "Default")
      (node (ref "A") (pin "19") (pinfunction "STBY_19") (pintype "passive"))
      (node (ref "A") (pin "20") (pinfunction "Vcc_20") (pintype "passive"))
      (node (ref "B") (pin "19") (pinfunction "STBY_19") (pintype "passive"))
      (node (ref "B") (pin "20") (pinfunction "Vcc_20") (pintype "passive"))
      (node (ref "C1") (pin "1") (pinfunction "1_1") (pintype "passive"))
      (node (ref "C10") (pin "1") (pinfunction "1_1") (pintype "passive"))
      (node (ref "C11") (pin "1") (pinfunction "1_1") (pintype "passive"))
      (node (ref "C14") (pin "1") (pinfunction "1_1") (pintype "passive"))
      (node (ref "C15") (pin "1") (pinfunction "1_1") (pintype "passive"))
      (node (ref "C2") (pin "1") (pinfunction "1_1") (pintype "passive"))
      (node (ref "C3") (pin "1") (pinfunction "1_1") (pintype "passive"))
      (node (ref "C32") (pin "1") (pinfunction "1_1") (pintype "passive"))
      (node (ref "C4") (pin "1") (pinfunction "1_1") (pintype "passive"))
      (node (ref "C7") (pin "1") (pinfunction "1_1") (pintype "passive"))
      (node (ref "C71") (pin "1") (pinfunction "1_1") (pintype "passive"))
      (node (ref "C72") (pin "1") (pinfunction "1_1") (pintype "passive"))
      (node (ref "CEWKA") (pin "2") (pinfunction "2_2") (pintype "passive"))
      (node (ref "D21") (pin "2") (pinfunction "K_2") (pintype "passive"))
      (node (ref "J3") (pin "1") (pinfunction "1_1") (pintype "passive"))
      (node (ref "J4") (pin "1") (pinfunction "1_1") (pintype "passive"))
      (node (ref "JP1") (pin "1") (pinfunction "1_1") (pintype "passive"))
      (node (ref "LED2") (pin "2") (pinfunction "A_2") (pintype "passive"))
      (node (ref "LED3") (pin "2") (pinfunction "A_2") (pintype "passive"))
      (node (ref "LED4") (pin "2") (pinfunction "A_2") (pintype "passive"))
      (node (ref "LED5") (pin "2") (pinfunction "A_2") (pintype "passive"))
      (node (ref "LED6") (pin "2") (pinfunction "A_2") (pintype "passive"))
      (node (ref "LED7") (pin "2") (pinfunction "A_2") (pintype "passive"))
      (node (ref "LED8") (pin "2") (pinfunction "A_2") (pintype "passive"))
      (node (ref "LED9") (pin "2") (pinfunction "A_2") (pintype "passive"))
      (node (ref "Q0") (pin "1") (pinfunction "VBAT_1") (pintype "passive"))
      (node (ref "Q0") (pin "19") (pinfunction "VDD_4_19") (pintype "passive"))
      (node (ref "Q0") (pin "32") (pinfunction "VDD_2_32") (pintype "passive"))
      (node (ref "Q0") (pin "48") (pinfunction "VDD_3_48") (pintype "passive"))
      (node (ref "Q0") (pin "64") (pinfunction "VDD_1_64") (pintype "passive"))
      (node (ref "Q11") (pin "1") (pinfunction "Vdd_IO_1") (pintype "passive"))
      (node (ref "Q11") (pin "15") (pinfunction "Vdd_15") (pintype "passive"))
      (node (ref "Q11") (pin "16") (pinfunction "Vdd_16") (pintype "passive"))
      (node (ref "Q11") (pin "4") (pinfunction "SDO/SA0_4") (pintype "passive"))
      (node (ref "Q11") (pin "5") (pinfunction "CS_5") (pintype "passive"))
      (node (ref "Q2") (pin "3") (pinfunction "3V3_3") (pintype "passive"))
      (node (ref "Q8") (pin "OUT") (pinfunction "OUT_OUT") (pintype "passive"))
      (node (ref "R42") (pin "2") (pinfunction "2_2") (pintype "passive"))
      (node (ref "R66") (pin "1") (pinfunction "1_1") (pintype "passive"))
      (node (ref "R67") (pin "1") (pinfunction "1_1") (pintype "passive"))
    )
    (net (code "90") (name "unconnected-(Q0-PA3-Pad17)") (class "Default")
      (node (ref "Q0") (pin "17") (pinfunction "PA3_17") (pintype "passive"))
    )
    (net (code "91") (name "unconnected-(Q0-PB0-Pad26)") (class "Default")
      (node (ref "Q0") (pin "26") (pinfunction "PB0_26") (pintype "passive"))
    )
    (net (code "92") (name "unconnected-(Q0-PB1-Pad27)") (class "Default")
      (node (ref "Q0") (pin "27") (pinfunction "PB1_27") (pintype "passive"))
    )
    (net (code "93") (name "unconnected-(Q0-PB8-Pad61)") (class "Default")
      (node (ref "Q0") (pin "61") (pinfunction "PB8_61") (pintype "passive"))
    )
    (net (code "94") (name "unconnected-(Q0-PB9-Pad62)") (class "Default")
      (node (ref "Q0") (pin "62") (pinfunction "PB9_62") (pintype "passive"))
    )
    (net (code "95") (name "unconnected-(Q0-PC11-Pad52)") (class "Default")
      (node (ref "Q0") (pin "52") (pinfunction "PC11_52") (pintype "passive"))
    )
    (net (code "96") (name "unconnected-(Q0-PC15{slash}OSC32_OUT-Pad4)") (class "Default")
      (node (ref "Q0") (pin "4") (pinfunction "PC15/OSC32_OUT_4") (pintype "passive"))
    )
    (net (code "97") (name "unconnected-(Q0-PD2-Pad54)") (class "Default")
      (node (ref "Q0") (pin "54") (pinfunction "PD2_54") (pintype "passive"))
    )
    (net (code "98") (name "unconnected-(Q0-PF4-Pad18)") (class "Default")
      (node (ref "Q0") (pin "18") (pinfunction "PF4_18") (pintype "passive"))
    )
    (net (code "99") (name "unconnected-(S1-Pad3)") (class "Default")
      (node (ref "S1") (pin "3") (pintype "passive"))
    )
    (net (code "100") (name "unconnected-(S2-Pad1)") (class "Default")
      (node (ref "S2") (pin "1") (pintype "passive"))
    )
    (net (code "101") (name "unconnected-(S3-Pad1)") (class "Default")
      (node (ref "S3") (pin "1") (pintype "passive"))
    )
  )
)
